# Leuchtende_Untertasse.net
KiCad netlist of a schematic drawn in EAGLE
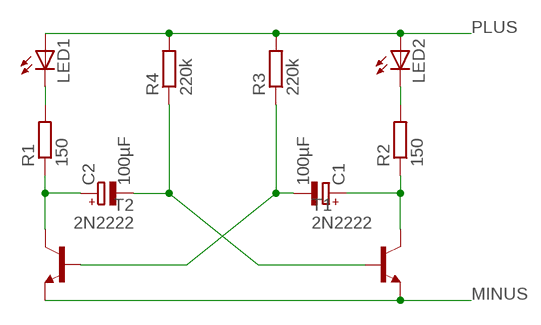
[diagram p0: schematic, sheet 1]

(export (version "E")
  (design (tool "Eeschema 10.0.6"))
  (components
    (comp (ref "C1")
      (value "100µF")
      (footprint "eagle-import:E2,5-5")
      (libsource (lib "eagle-import") (part "CPOL-EUE2.5-5"))
    )
    (comp (ref "C2")
      (value "100µF")
      (footprint "eagle-import:E2,5-5")
      (libsource (lib "eagle-import") (part "CPOL-EUE2.5-5"))
    )
    (comp (ref "LED1")
      (value "LED5MM")
      (footprint "eagle-import:LED5MM")
      (libsource (lib "eagle-import") (part "LED5MM"))
    )
    (comp (ref "LED2")
      (value "LED5MM")
      (footprint "eagle-import:LED5MM")
      (libsource (lib "eagle-import") (part "LED5MM"))
    )
    (comp (ref "R1")
      (value "150")
      (footprint "eagle-import:0204_7")
      (libsource (lib "eagle-import") (part "R-EU_0204/7"))
    )
    (comp (ref "R2")
      (value "150")
      (footprint "eagle-import:0204_7")
      (libsource (lib "eagle-import") (part "R-EU_0204/7"))
    )
    (comp (ref "R3")
      (value "220k")
      (footprint "eagle-import:0204_7")
      (libsource (lib "eagle-import") (part "R-EU_0204/7"))
    )
    (comp (ref "R4")
      (value "220k")
      (footprint "eagle-import:0204_7")
      (libsource (lib "eagle-import") (part "R-EU_0204/7"))
    )
    (comp (ref "T1")
      (value "2N2222")
      (footprint "eagle-import:TO18")
      (libsource (lib "eagle-import") (part "2N2222"))
    )
    (comp (ref "T2")
      (value "2N2222")
      (footprint "eagle-import:TO18")
      (libsource (lib "eagle-import") (part "2N2222"))
    )
  )
  (nets
    (net (code "1") (name "/MINUS") (class "Default")
      (node (ref "T1") (pin "1") (pinfunction "E_1") (pintype "passive"))
      (node (ref "T2") (pin "1") (pinfunction "E_1") (pintype "passive"))
    )
    (net (code "2") (name "/PLUS") (class "Default")
      (node (ref "LED1") (pin "A") (pinfunction "A_A") (pintype "passive"))
      (node (ref "LED2") (pin "A") (pinfunction "A_A") (pintype "passive"))
      (node (ref "R3") (pin "2") (pinfunction "2_2") (pintype "passive"))
      (node (ref "R4") (pin "2") (pinfunction "2_2") (pintype "passive"))
    )
    (net (code "3") (name "Net-(LED1-C)") (class "Default")
      (node (ref "LED1") (pin "K") (pinfunction "C_K") (pintype "passive"))
      (node (ref "R1") (pin "2") (pinfunction "2_2") (pintype "passive"))
    )
    (net (code "4") (name "Net-(LED2-C)") (class "Default")
      (node (ref "LED2") (pin "K") (pinfunction "C_K") (pintype "passive"))
      (node (ref "R2") (pin "2") (pinfunction "2_2") (pintype "passive"))
    )
    (net (code "5") (name "Net-(T1-B)") (class "Default")
      (node (ref "C2") (pin "-") (pinfunction "-_-") (pintype "passive"))
      (node (ref "R4") (pin "1") (pinfunction "1_1") (pintype "passive"))
      (node (ref "T1") (pin "2") (pinfunction "B_2") (pintype "passive"))
    )
    (net (code "6") (name "Net-(T1-C)") (class "Default")
      (node (ref "C1") (pin "+") (pinfunction "+_+") (pintype "passive"))
      (node (ref "R2") (pin "1") (pinfunction "1_1") (pintype "passive"))
      (node (ref "T1") (pin "3") (pinfunction "C_3") (pintype "passive"))
    )
    (net (code "7") (name "Net-(T2-B)") (class "Default")
      (node (ref "C1") (pin "-") (pinfunction "-_-") (pintype "passive"))
      (node (ref "R3") (pin "1") (pinfunction "1_1") (pintype "passive"))
      (node (ref "T2") (pin "2") (pinfunction "B_2") (pintype "passive"))
    )
    (net (code "8") (name "Net-(T2-C)") (class "Default")
      (node (ref "C2") (pin "+") (pinfunction "+_+") (pintype "passive"))
      (node (ref "R1") (pin "1") (pinfunction "1_1") (pintype "passive"))
      (node (ref "T2") (pin "3") (pinfunction "C_3") (pintype "passive"))
    )
  )
)
